# dual_power_supply.net
KiCad netlist of a schematic drawn in EAGLE
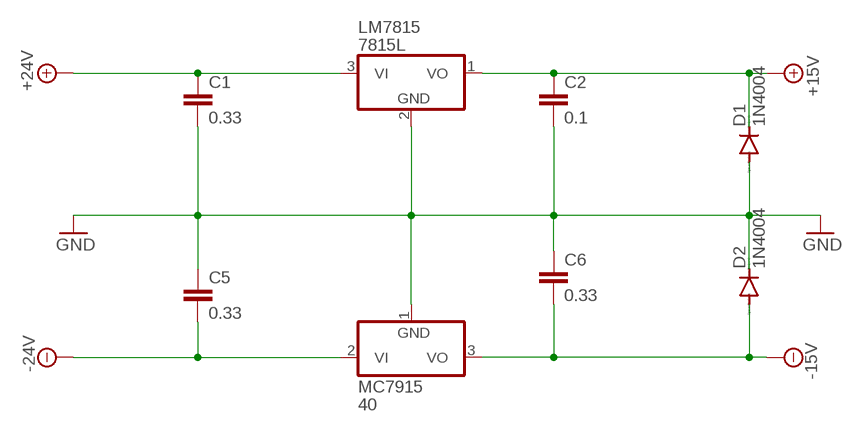
[diagram p0: schematic, sheet 1]

(export (version "E")
  (design (tool "Eeschema 10.0.6"))
  (components
    (comp (ref "C1")
      (value "0.33")
      (footprint "eagle-import:C2.5-3")
      (libsource (lib "eagle-import") (part "C2,5-3"))
    )
    (comp (ref "C2")
      (value "0.1")
      (footprint "eagle-import:C2.5-3")
      (libsource (lib "eagle-import") (part "C2,5-3"))
    )
    (comp (ref "C5")
      (value "0.33")
      (footprint "eagle-import:C2.5-3")
      (libsource (lib "eagle-import") (part "C2,5-3"))
    )
    (comp (ref "C6")
      (value "0.33")
      (footprint "eagle-import:C2.5-3")
      (libsource (lib "eagle-import") (part "C2,5-3"))
    )
    (comp (ref "D1")
      (value "1N4004")
      (footprint "eagle-import:DO41-10")
      (libsource (lib "eagle-import") (part "1N4004"))
    )
    (comp (ref "D2")
      (value "1N4004")
      (footprint "eagle-import:DO41-10")
      (libsource (lib "eagle-import") (part "1N4004"))
    )
    (comp (ref "LM7815")
      (value "7815L")
      (footprint "eagle-import:TO92")
      (libsource (lib "eagle-import") (part "78L15"))
    )
    (comp (ref "MC7915")
      (value "40")
      (footprint "eagle-import:TO92")
      (libsource (lib "eagle-import") (part "79L15"))
    )
  )
  (nets
    (net (code "1") (name "+15V") (class "Default")
      (node (ref "C2") (pin "1") (pinfunction "1_1") (pintype "passive"))
      (node (ref "D1") (pin "C") (pinfunction "C_C") (pintype "passive"))
      (node (ref "LM7815") (pin "1") (pinfunction "VO_1") (pintype "passive"))
    )
    (net (code "2") (name "+24V") (class "Default")
      (node (ref "C1") (pin "1") (pinfunction "1_1") (pintype "passive"))
      (node (ref "LM7815") (pin "3") (pinfunction "VI_3") (pintype "input"))
    )
    (net (code "3") (name "-15V") (class "Default")
      (node (ref "C6") (pin "2") (pinfunction "2_2") (pintype "passive"))
      (node (ref "D2") (pin "A") (pinfunction "A_A") (pintype "passive"))
      (node (ref "MC7915") (pin "3") (pinfunction "VO_3") (pintype "passive"))
    )
    (net (code "4") (name "-24V") (class "Default")
      (node (ref "C5") (pin "2") (pinfunction "2_2") (pintype "passive"))
      (node (ref "MC7915") (pin "2") (pinfunction "VI_2") (pintype "input"))
    )
    (net (code "5") (name "GND") (class "Default")
      (node (ref "C1") (pin "2") (pinfunction "2_2") (pintype "passive"))
      (node (ref "C2") (pin "2") (pinfunction "2_2") (pintype "passive"))
      (node (ref "C5") (pin "1") (pinfunction "1_1") (pintype "passive"))
      (node (ref "C6") (pin "1") (pinfunction "1_1") (pintype "passive"))
      (node (ref "D1") (pin "A") (pinfunction "A_A") (pintype "passive"))
      (node (ref "D2") (pin "C") (pinfunction "C_C") (pintype "passive"))
      (node (ref "LM7815") (pin "2") (pinfunction "GND_2") (pintype "passive"))
      (node (ref "MC7915") (pin "1") (pinfunction "GND_1") (pintype "passive"))
    )
  )
)
